# CPU_Logic.net
KiCad netlist of a schematic drawn in Altium Designer
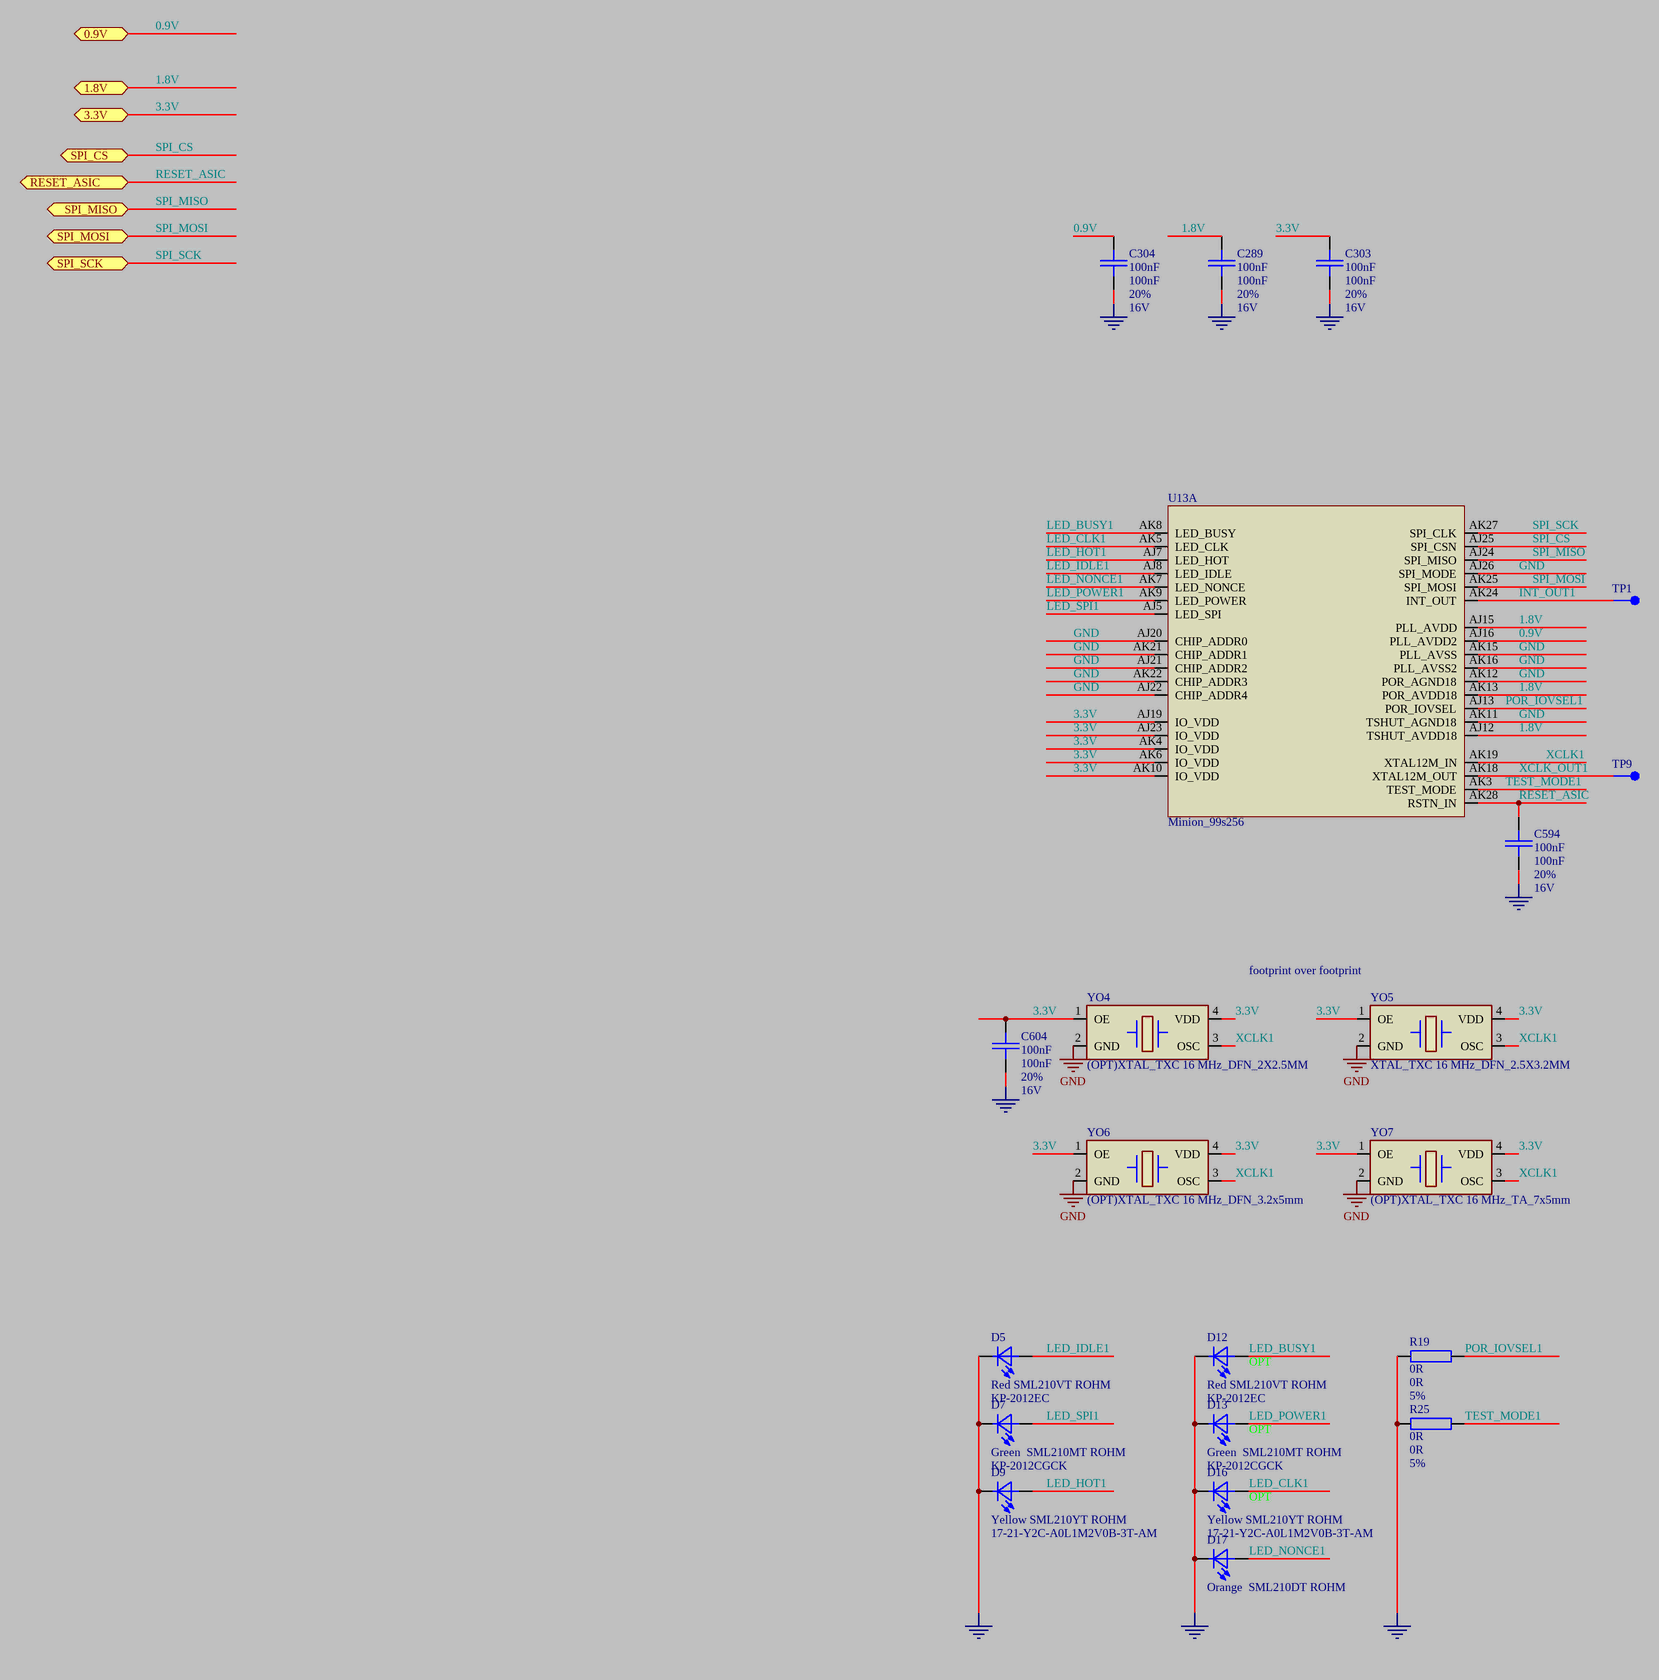
[diagram p0: CPU_Logic.SchDoc]

(export (version "E")
  (design (tool "Eeschema 10.0.6"))
  (components
    (comp (ref "C289")
      (value "100nF")
      (footprint "SMD_0603_CAPC1608X95N")
      (fields
        (field (name "DB_PART_NUMBER") "CAP000027236")
        (field (name "DB_VALUE") "100nF")
        (field (name "DB_TOLERANCE") "20%")
        (field (name "DB_VOLTAGE") "16V")
        (field (name "DB_MANUFACTURER_PART") "KEMET    C0603C104M4RAC")
        (field (name "DB_APPROVED_BY") "ISHIDDEN=T")
      )
      (libsource (lib "Database_Libs1") (part "C"))
    )
    (comp (ref "C303")
      (value "100nF")
      (footprint "SMD_0603_CAPC1608X95N")
      (fields
        (field (name "DB_PART_NUMBER") "CAP000027236")
        (field (name "DB_VALUE") "100nF")
        (field (name "DB_TOLERANCE") "20%")
        (field (name "DB_VOLTAGE") "16V")
        (field (name "DB_MANUFACTURER_PART") "KEMET    C0603C104M4RAC")
        (field (name "DB_APPROVED_BY") "ISHIDDEN=T")
      )
      (libsource (lib "Database_Libs1") (part "C"))
    )
    (comp (ref "C304")
      (value "100nF")
      (footprint "SMD_0603_CAPC1608X95N")
      (fields
        (field (name "DB_PART_NUMBER") "CAP000027236")
        (field (name "DB_VALUE") "100nF")
        (field (name "DB_TOLERANCE") "20%")
        (field (name "DB_VOLTAGE") "16V")
        (field (name "DB_MANUFACTURER_PART") "KEMET    C0603C104M4RAC")
        (field (name "DB_APPROVED_BY") "ISHIDDEN=T")
      )
      (libsource (lib "Database_Libs1") (part "C"))
    )
    (comp (ref "C594")
      (value "100nF")
      (footprint "SMD_0603_CAPC1608X95N")
      (fields
        (field (name "DB_PART_NUMBER") "CAP000027236")
        (field (name "DB_VALUE") "100nF")
        (field (name "DB_TOLERANCE") "20%")
        (field (name "DB_VOLTAGE") "16V")
        (field (name "DB_MANUFACTURER_PART") "KEMET    C0603C104M4RAC")
        (field (name "DB_APPROVED_BY") "ISHIDDEN=T")
      )
      (libsource (lib "Database_Libs1") (part "C"))
    )
    (comp (ref "C604")
      (value "100nF")
      (footprint "SMD_0603_CAPC1608X95N")
      (fields
        (field (name "DB_PART_NUMBER") "CAP000027236")
        (field (name "DB_VALUE") "100nF")
        (field (name "DB_TOLERANCE") "20%")
        (field (name "DB_VOLTAGE") "16V")
        (field (name "DB_MANUFACTURER_PART") "KEMET    C0603C104M4RAC")
        (field (name "DB_APPROVED_BY") "ISHIDDEN=T")
      )
      (libsource (lib "Database_Libs1") (part "C"))
    )
    (comp (ref "D5")
      (value "Red SML210VT ROHM")
      (footprint "SMD_0805_LED2012X100N")
      (fields
        (field (name "DB_PART_NUMBER") "OPT000000095")
        (field (name "DB_MANUFACTURER_PART") "KINGBRIGHT       KP-2012EC")
        (field (name "DB_VALUE") "KP-2012EC")
        (field (name "DB_APPROVED_BY") "VSN")
      )
      (libsource (lib "Database_Libs1") (part "LED"))
    )
    (comp (ref "D7")
      (value "Green  SML210MT ROHM")
      (footprint "SMD_0805_LED2012X100N")
      (fields
        (field (name "DB_PART_NUMBER") "OPT000000096")
        (field (name "DB_MANUFACTURER_PART") "KINGBRIGHT       KP-2012CGCK")
        (field (name "DB_VALUE") "KP-2012CGCK")
        (field (name "DB_APPROVED_BY") "VSN")
      )
      (libsource (lib "Database_Libs1") (part "LED"))
    )
    (comp (ref "D9")
      (value "Yellow SML210YT ROHM")
      (footprint "SMD_0805_LED2012X100N")
      (fields
        (field (name "DB_PART_NUMBER") "OPT000000092")
        (field (name "DB_MANUFACTURER_PART") "EVERLIGHT       17-21-Y2C-A0L1M2V0B-3T-AM")
        (field (name "DB_VALUE") "17-21-Y2C-A0L1M2V0B-3T-AM")
        (field (name "DB_APPROVED_BY") "VSN")
      )
      (libsource (lib "Database_Libs1") (part "LED"))
    )
    (comp (ref "D12")
      (value "Red SML210VT ROHM")
      (footprint "SMD_0805_LED2012X100N")
      (fields
        (field (name "DB_PART_NUMBER") "OPT000000095")
        (field (name "DB_MANUFACTURER_PART") "KINGBRIGHT       KP-2012EC")
        (field (name "DB_VALUE") "KP-2012EC")
        (field (name "DB_APPROVED_BY") "VSN")
      )
      (libsource (lib "Database_Libs1") (part "LED"))
    )
    (comp (ref "D13")
      (value "Green  SML210MT ROHM")
      (footprint "SMD_0805_LED2012X100N")
      (fields
        (field (name "DB_PART_NUMBER") "OPT000000096")
        (field (name "DB_MANUFACTURER_PART") "KINGBRIGHT       KP-2012CGCK")
        (field (name "DB_VALUE") "KP-2012CGCK")
        (field (name "DB_APPROVED_BY") "VSN")
      )
      (libsource (lib "Database_Libs1") (part "LED"))
    )
    (comp (ref "D16")
      (value "Yellow SML210YT ROHM")
      (footprint "SMD_0805_LED2012X100N")
      (fields
        (field (name "DB_PART_NUMBER") "OPT000000092")
        (field (name "DB_MANUFACTURER_PART") "EVERLIGHT       17-21-Y2C-A0L1M2V0B-3T-AM")
        (field (name "DB_VALUE") "17-21-Y2C-A0L1M2V0B-3T-AM")
        (field (name "DB_APPROVED_BY") "VSN")
      )
      (libsource (lib "Database_Libs1") (part "LED"))
    )
    (comp (ref "D17")
      (value "Orange  SML210DT ROHM")
      (footprint "SMD_0805_LED2012X100N")
      (fields
        (field (name "DB_PART_NUMBER") "OPT000000096")
        (field (name "DB_MANUFACTURER_PART") "KINGBRIGHT       KP-2012CGCK")
        (field (name "DB_APPROVED_BY") "VSN")
      )
      (libsource (lib "altium-import") (part "root_0_LED_Orange_"))
    )
    (comp (ref "R19")
      (value "0R")
      (footprint "SMD_0603_RESC1608X55N")
      (fields
        (field (name "DB_PART_NUMBER") "RES000006349")
        (field (name "DB_VALUE") "0R")
        (field (name "DB_TOLERANCE") "5%")
        (field (name "DB_MANUFACTURER_PART") "YAGEO    RC0603JR-070R")
        (field (name "DB_APPROVED_BY") "ISHIDDEN=T")
      )
      (libsource (lib "Database_Libs1") (part "R"))
    )
    (comp (ref "R25")
      (value "0R")
      (footprint "SMD_0603_RESC1608X55N")
      (fields
        (field (name "DB_PART_NUMBER") "RES000006349")
        (field (name "DB_VALUE") "0R")
        (field (name "DB_TOLERANCE") "5%")
        (field (name "DB_MANUFACTURER_PART") "YAGEO    RC0603JR-070R")
        (field (name "DB_APPROVED_BY") "ISHIDDEN=T")
      )
      (libsource (lib "Database_Libs1") (part "R"))
    )
    (comp (ref "TP1")
      (value "TEST_POINT_1")
      (footprint "SMD_TP_100-254")
      (fields
        (field (name "DB_PART_NUMBER") "TPO000000001")
        (field (name "DB_MANUFACTURER_PART") "ISHIDDEN=T")
        (field (name "DB_APPROVED_BY") "ISHIDDEN=T")
      )
      (libsource (lib "Database_Libs1") (part "TEST_POINT_1"))
    )
    (comp (ref "TP9")
      (value "TEST_POINT_1")
      (footprint "SMD_TP_100-254")
      (fields
        (field (name "DB_PART_NUMBER") "TPO000000001")
        (field (name "DB_MANUFACTURER_PART") "ISHIDDEN=T")
        (field (name "DB_APPROVED_BY") "ISHIDDEN=T")
      )
      (libsource (lib "Database_Libs1") (part "TEST_POINT_1"))
    )
    (comp (ref "U13")
      (value "Minion_99s256")
      (footprint "SMD_BGA900C80P30X30")
      (libsource (lib "BitCoin") (part "Minion_99s256"))
    )
    (comp (ref "YO4")
      (value "(OPT)XTAL_TXC 16 MHz_DFN_2X2.5MM")
      (footprint "SMD_OSCCF200X250X90-4N")
      (libsource (lib "Schlib1") (part "SMD_OSC_DFN_2X2.5MM"))
    )
    (comp (ref "YO5")
      (value "XTAL_TXC 16 MHz_DFN_2.5X3.2MM")
      (footprint "SMD_OSCCF250X320X90-4N")
      (libsource (lib "Schlib1") (part "SMD_OSC_DFN_2.5X3.2MM"))
    )
    (comp (ref "YO6")
      (value "(OPT)XTAL_TXC 16 MHz_DFN_3.2x5mm")
      (footprint "SMD_OSCCF320X400X90-4N")
      (libsource (lib "Schlib1") (part "SMD_OSC_DFN_3.2x5mm"))
    )
    (comp (ref "YO7")
      (value "(OPT)XTAL_TXC 16 MHz_TA_7x5mm")
      (footprint "SMD_OSCCC500X700X100-4N")
      (libsource (lib "BitCoin") (part "SMD_OSC_TA_7x5mm"))
    )
  )
  (nets
    (net (code "1") (name "/0.9V") (class "Default")
      (node (ref "C304") (pin "2") (pinfunction "2_2") (pintype "passive"))
      (node (ref "U13") (pin "AJ16") (pinfunction "PLL_AVDD2_AJ16") (pintype "passive"))
    )
    (net (code "2") (name "/1.8V") (class "Default")
      (node (ref "C289") (pin "2") (pinfunction "2_2") (pintype "passive"))
      (node (ref "U13") (pin "AJ12") (pinfunction "TSHUT_AVDD18_AJ12") (pintype "passive"))
      (node (ref "U13") (pin "AJ15") (pinfunction "PLL_AVDD_AJ15") (pintype "passive"))
      (node (ref "U13") (pin "AK13") (pinfunction "POR_AVDD18_AK13") (pintype "passive"))
    )
    (net (code "3") (name "/3.3V") (class "Default")
      (node (ref "C303") (pin "2") (pinfunction "2_2") (pintype "passive"))
      (node (ref "C604") (pin "1") (pinfunction "1_1") (pintype "passive"))
      (node (ref "U13") (pin "AJ19") (pinfunction "IO_VDD_AJ19") (pintype "passive"))
      (node (ref "U13") (pin "AJ23") (pinfunction "IO_VDD_AJ23") (pintype "passive"))
      (node (ref "U13") (pin "AK10") (pinfunction "IO_VDD_AK10") (pintype "passive"))
      (node (ref "U13") (pin "AK4") (pinfunction "IO_VDD_AK4") (pintype "passive"))
      (node (ref "U13") (pin "AK6") (pinfunction "IO_VDD_AK6") (pintype "passive"))
      (node (ref "YO4") (pin "1") (pinfunction "OE_1") (pintype "passive"))
      (node (ref "YO4") (pin "4") (pinfunction "VDD_4") (pintype "passive"))
      (node (ref "YO5") (pin "1") (pinfunction "OE_1") (pintype "passive"))
      (node (ref "YO5") (pin "4") (pinfunction "VDD_4") (pintype "passive"))
      (node (ref "YO6") (pin "1") (pinfunction "OE_1") (pintype "passive"))
      (node (ref "YO6") (pin "4") (pinfunction "VDD_4") (pintype "passive"))
      (node (ref "YO7") (pin "1") (pinfunction "OE_1") (pintype "passive"))
      (node (ref "YO7") (pin "4") (pinfunction "VDD_4") (pintype "passive"))
    )
    (net (code "4") (name "/INT_OUT1") (class "Default")
      (node (ref "TP1") (pin "1") (pinfunction "1_1") (pintype "passive"))
      (node (ref "U13") (pin "AK24") (pinfunction "INT_OUT_AK24") (pintype "passive"))
    )
    (net (code "5") (name "/LED_BUSY1") (class "Default")
      (node (ref "D12") (pin "2") (pinfunction "A_2") (pintype "passive"))
      (node (ref "U13") (pin "AK8") (pinfunction "LED_BUSY_AK8") (pintype "passive"))
    )
    (net (code "6") (name "/LED_CLK1") (class "Default")
      (node (ref "D16") (pin "2") (pinfunction "A_2") (pintype "passive"))
      (node (ref "U13") (pin "AK5") (pinfunction "LED_CLK_AK5") (pintype "passive"))
    )
    (net (code "7") (name "/LED_HOT1") (class "Default")
      (node (ref "D9") (pin "2") (pinfunction "A_2") (pintype "passive"))
      (node (ref "U13") (pin "AJ7") (pinfunction "LED_HOT_AJ7") (pintype "passive"))
    )
    (net (code "8") (name "/LED_IDLE1") (class "Default")
      (node (ref "D5") (pin "2") (pinfunction "A_2") (pintype "passive"))
      (node (ref "U13") (pin "AJ8") (pinfunction "LED_IDLE_AJ8") (pintype "passive"))
    )
    (net (code "9") (name "/LED_NONCE1") (class "Default")
      (node (ref "D17") (pin "2") (pinfunction "A_2") (pintype "passive"))
      (node (ref "U13") (pin "AK7") (pinfunction "LED_NONCE_AK7") (pintype "passive"))
    )
    (net (code "10") (name "/LED_POWER1") (class "Default")
      (node (ref "D13") (pin "2") (pinfunction "A_2") (pintype "passive"))
      (node (ref "U13") (pin "AK9") (pinfunction "LED_POWER_AK9") (pintype "passive"))
    )
    (net (code "11") (name "/LED_SPI1") (class "Default")
      (node (ref "D7") (pin "2") (pinfunction "A_2") (pintype "passive"))
      (node (ref "U13") (pin "AJ5") (pinfunction "LED_SPI_AJ5") (pintype "passive"))
    )
    (net (code "12") (name "/POR_IOVSEL1") (class "Default")
      (node (ref "R19") (pin "2") (pinfunction "2_2") (pintype "passive"))
      (node (ref "U13") (pin "AJ13") (pinfunction "POR_IOVSEL_AJ13") (pintype "passive"))
    )
    (net (code "13") (name "/RESET_ASIC") (class "Default")
      (node (ref "C594") (pin "1") (pinfunction "1_1") (pintype "passive"))
      (node (ref "U13") (pin "AK28") (pinfunction "RSTN_IN_AK28") (pintype "passive"))
    )
    (net (code "14") (name "/SPI_CS") (class "Default")
      (node (ref "U13") (pin "AJ25") (pinfunction "SPI_CSN_AJ25") (pintype "passive"))
    )
    (net (code "15") (name "/SPI_MISO") (class "Default")
      (node (ref "U13") (pin "AJ24") (pinfunction "SPI_MISO_AJ24") (pintype "passive"))
    )
    (net (code "16") (name "/SPI_MOSI") (class "Default")
      (node (ref "U13") (pin "AK25") (pinfunction "SPI_MOSI_AK25") (pintype "passive"))
    )
    (net (code "17") (name "/SPI_SCK") (class "Default")
      (node (ref "U13") (pin "AK27") (pinfunction "SPI_CLK_AK27") (pintype "passive"))
    )
    (net (code "18") (name "/TEST_MODE1") (class "Default")
      (node (ref "R25") (pin "2") (pinfunction "2_2") (pintype "passive"))
      (node (ref "U13") (pin "AK3") (pinfunction "TEST_MODE_AK3") (pintype "passive"))
    )
    (net (code "19") (name "/XCLK1") (class "Default")
      (node (ref "U13") (pin "AK19") (pinfunction "XTAL12M_IN_AK19") (pintype "passive"))
      (node (ref "YO4") (pin "3") (pinfunction "OSC_3") (pintype "passive"))
      (node (ref "YO5") (pin "3") (pinfunction "OSC_3") (pintype "passive"))
      (node (ref "YO6") (pin "3") (pinfunction "OSC_3") (pintype "passive"))
      (node (ref "YO7") (pin "3") (pinfunction "OSC_3") (pintype "passive"))
    )
    (net (code "20") (name "/XCLK_OUT1") (class "Default")
      (node (ref "TP9") (pin "1") (pinfunction "1_1") (pintype "passive"))
      (node (ref "U13") (pin "AK18") (pinfunction "XTAL12M_OUT_AK18") (pintype "passive"))
    )
    (net (code "21") (name "GND") (class "Default")
      (node (ref "C289") (pin "1") (pinfunction "1_1") (pintype "passive"))
      (node (ref "C303") (pin "1") (pinfunction "1_1") (pintype "passive"))
      (node (ref "C304") (pin "1") (pinfunction "1_1") (pintype "passive"))
      (node (ref "C594") (pin "2") (pinfunction "2_2") (pintype "passive"))
      (node (ref "C604") (pin "2") (pinfunction "2_2") (pintype "passive"))
      (node (ref "D12") (pin "1") (pinfunction "C_1") (pintype "passive"))
      (node (ref "D13") (pin "1") (pinfunction "C_1") (pintype "passive"))
      (node (ref "D16") (pin "1") (pinfunction "C_1") (pintype "passive"))
      (node (ref "D17") (pin "1") (pinfunction "C_1") (pintype "passive"))
      (node (ref "D5") (pin "1") (pinfunction "C_1") (pintype "passive"))
      (node (ref "D7") (pin "1") (pinfunction "C_1") (pintype "passive"))
      (node (ref "D9") (pin "1") (pinfunction "C_1") (pintype "passive"))
      (node (ref "R19") (pin "1") (pinfunction "1_1") (pintype "passive"))
      (node (ref "R25") (pin "1") (pinfunction "1_1") (pintype "passive"))
      (node (ref "U13") (pin "AJ20") (pinfunction "CHIP_ADDR0_AJ20") (pintype "passive"))
      (node (ref "U13") (pin "AJ21") (pinfunction "CHIP_ADDR2_AJ21") (pintype "passive"))
      (node (ref "U13") (pin "AJ22") (pinfunction "CHIP_ADDR4_AJ22") (pintype "passive"))
      (node (ref "U13") (pin "AJ26") (pinfunction "SPI_MODE_AJ26") (pintype "passive"))
      (node (ref "U13") (pin "AK11") (pinfunction "TSHUT_AGND18_AK11") (pintype "passive"))
      (node (ref "U13") (pin "AK12") (pinfunction "POR_AGND18_AK12") (pintype "passive"))
      (node (ref "U13") (pin "AK15") (pinfunction "PLL_AVSS_AK15") (pintype "passive"))
      (node (ref "U13") (pin "AK16") (pinfunction "PLL_AVSS2_AK16") (pintype "passive"))
      (node (ref "U13") (pin "AK21") (pinfunction "CHIP_ADDR1_AK21") (pintype "passive"))
      (node (ref "U13") (pin "AK22") (pinfunction "CHIP_ADDR3_AK22") (pintype "passive"))
      (node (ref "YO4") (pin "2") (pinfunction "GND_2") (pintype "passive"))
      (node (ref "YO5") (pin "2") (pinfunction "GND_2") (pintype "passive"))
      (node (ref "YO6") (pin "2") (pinfunction "GND_2") (pintype "passive"))
      (node (ref "YO7") (pin "2") (pinfunction "GND_2") (pintype "passive"))
    )
  )
)
